# 02_-_Microcontroller.net
KiCad netlist of a schematic drawn in Altium Designer
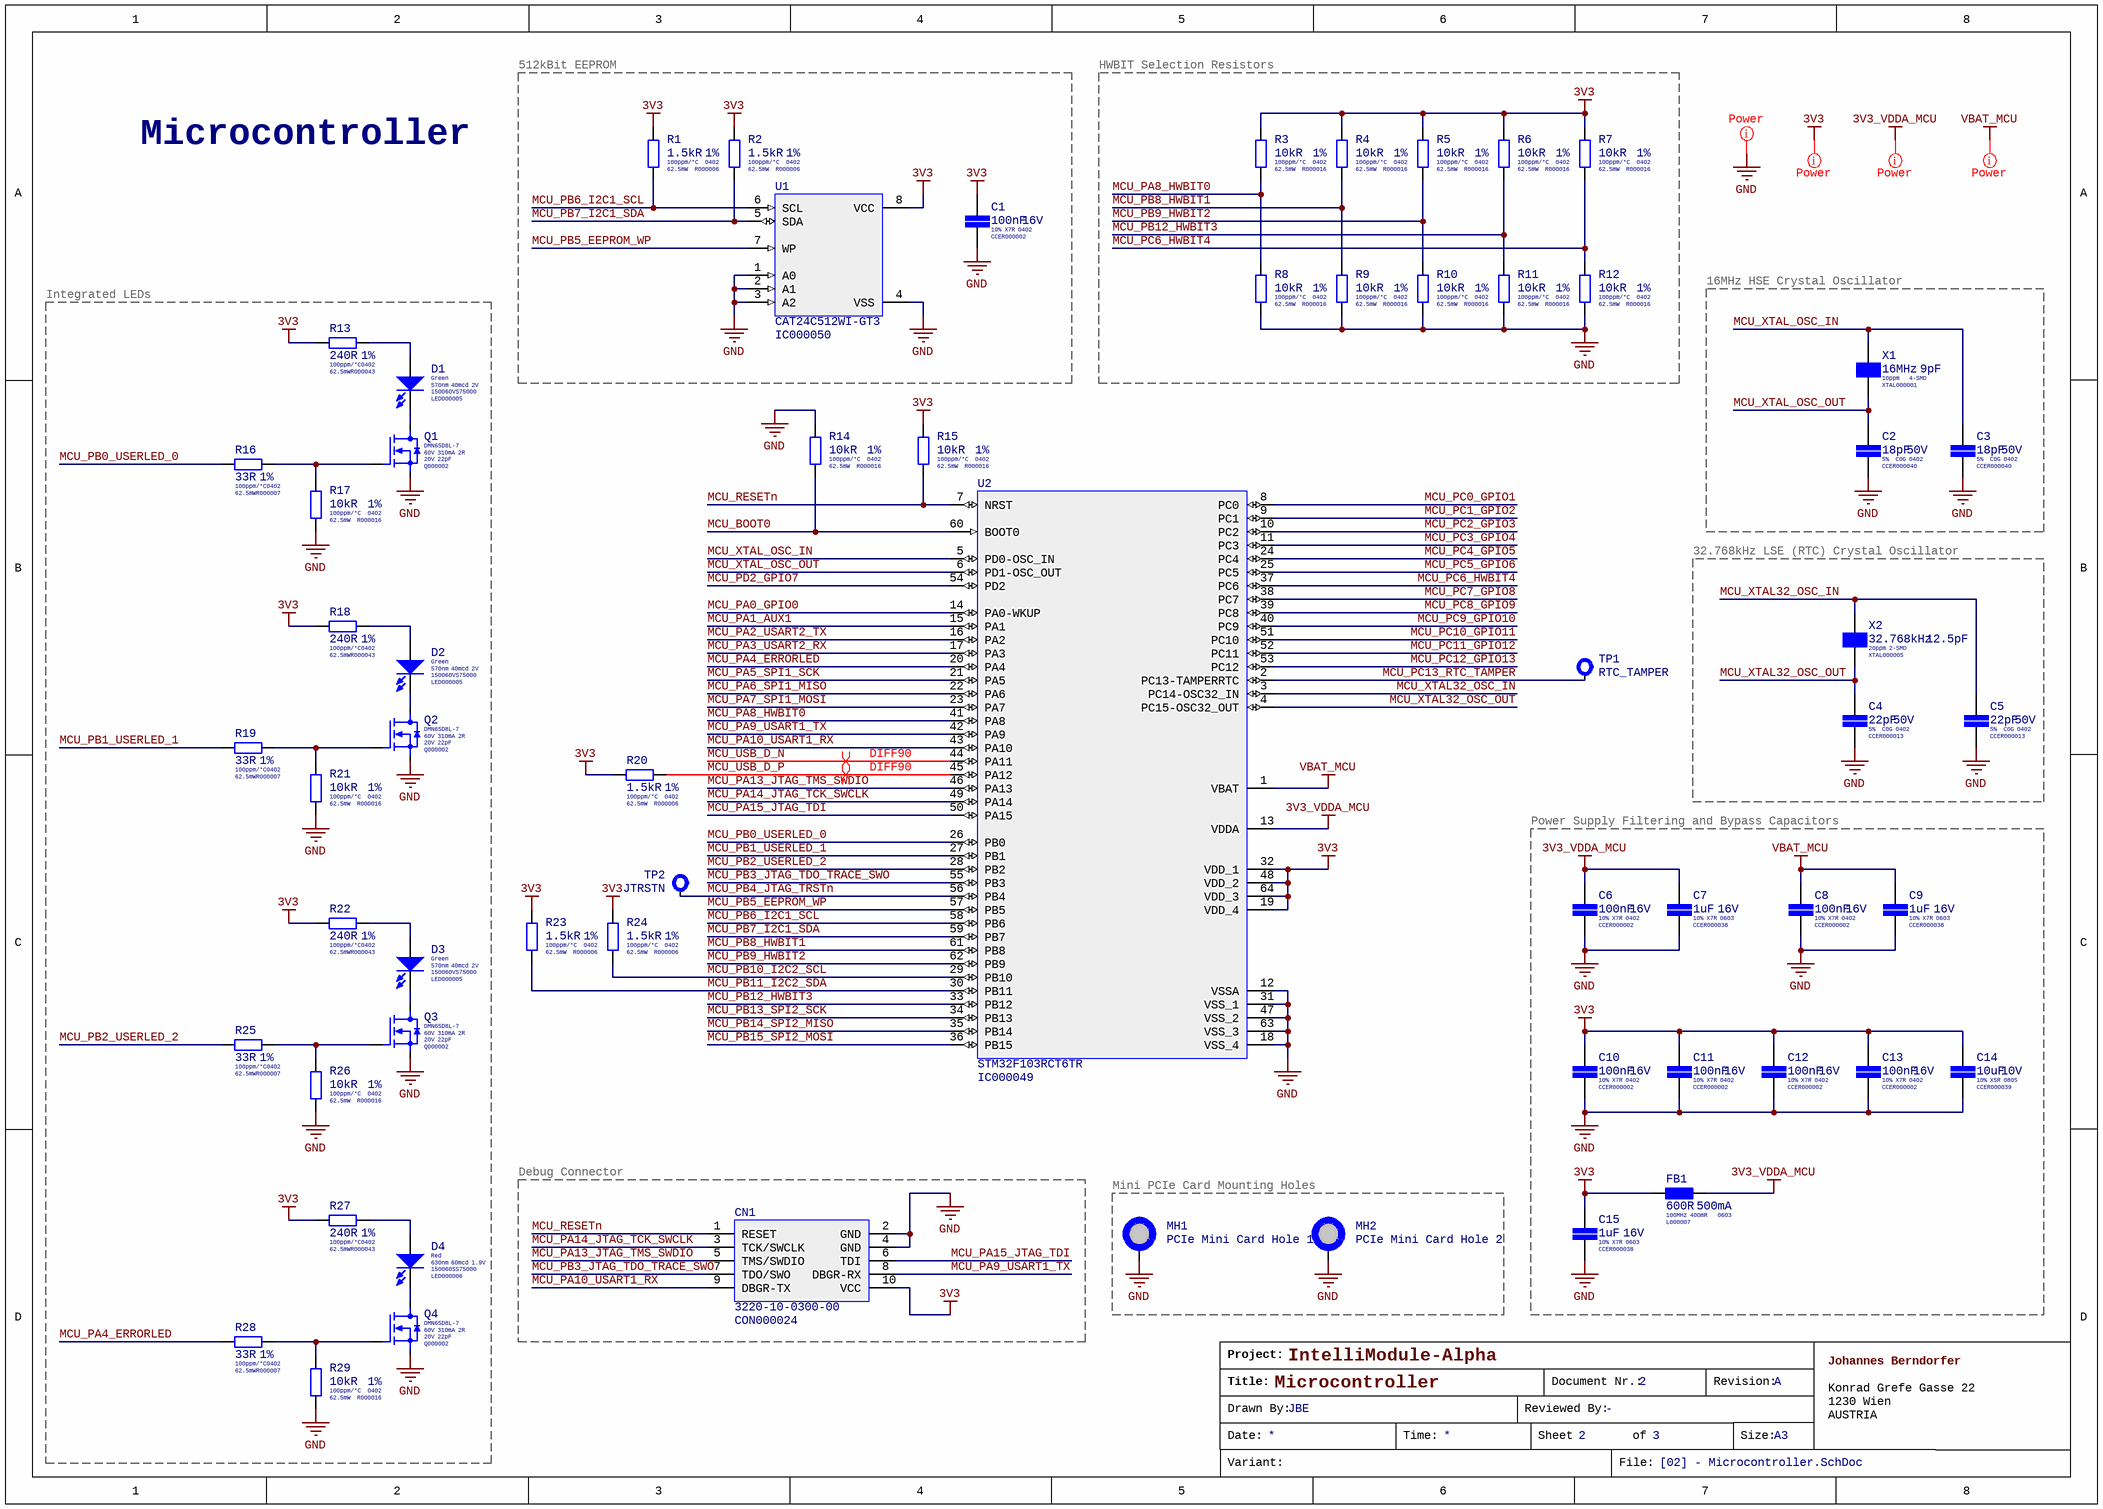
[diagram p0: [02] - Microcontroller.SchDoc]

(export (version "E")
  (design (tool "Eeschema 10.0.6"))
  (components
    (comp (ref "C1")
      (value "100nF 16V")
      (footprint "CAP-SMD-0402-0.55MM-IPC-MED")
      (description "CAP CER 100N 16V X7R 10% SMD 0402 125C SAMSUNG")
      (fields
        (field (name "VOLTAGE") "16V")
        (field (name "TOLERANCE") "10%")
        (field (name "INTERNAL PART NUMBER") "CCER000002")
        (field (name "VOLTAGE RATING (DC)") "16V")
        (field (name "DIELECTRIC") "X7R")
        (field (name "CASE/PACKAGE") "0402")
        (field (name "CAPACITANCE") "100nF")
      )
      (libsource (lib "Altium_Lib_Standard") (part "CL05B104KO5NNNC"))
    )
    (comp (ref "C2")
      (value "18pF 50V")
      (footprint "CAP-SMD-0402-0.55MM-IPC-MED")
      (description "CAP CER 18P 50V C0G 5% SMD 0402 125C YAGEO")
      (fields
        (field (name "VOLTAGE") "50V")
        (field (name "INTERNAL PART NUMBER") "CCER000040")
        (field (name "CASE/PACKAGE") "0402")
        (field (name "DIELECTRIC") "C0G")
        (field (name "TOLERANCE") "5%")
        (field (name "VOLTAGE RATING") "50V")
        (field (name "CAPACITANCE") "18pF")
      )
      (libsource (lib "Altium_Lib_Standard") (part "CC0402JRNPO9BN180"))
    )
    (comp (ref "C3")
      (value "18pF 50V")
      (footprint "CAP-SMD-0402-0.55MM-IPC-MED")
      (description "CAP CER 18P 50V C0G 5% SMD 0402 125C YAGEO")
      (fields
        (field (name "VOLTAGE") "50V")
        (field (name "INTERNAL PART NUMBER") "CCER000040")
        (field (name "CASE/PACKAGE") "0402")
        (field (name "DIELECTRIC") "C0G")
        (field (name "TOLERANCE") "5%")
        (field (name "VOLTAGE RATING") "50V")
        (field (name "CAPACITANCE") "18pF")
      )
      (libsource (lib "Altium_Lib_Standard") (part "CC0402JRNPO9BN180"))
    )
    (comp (ref "C4")
      (value "22pF 50V")
      (footprint "CAP-SMD-0402-0.55MM-IPC-MED")
      (description "CAP CER 22P 50V C0G 5% SMD 0402 125C SAMSUNG")
      (fields
        (field (name "MANUFACTURER") "Samsung")
        (field (name "MANUFACTURER PART NUMBER") "CL05C220JB5NNNC")
        (field (name "INTERNAL PART NUMBER") "CCER000013")
        (field (name "VOLTAGE RATING") "50V")
        (field (name "TOLERANCE") "5%")
        (field (name "DIELECTRIC") "C0G")
        (field (name "CASE/PACKAGE") "0402")
        (field (name "CAPACITANCE") "22pF")
      )
      (libsource (lib "Altium_Lib_Standard") (part "CL05C220JB5NNNC"))
    )
    (comp (ref "C5")
      (value "22pF 50V")
      (footprint "CAP-SMD-0402-0.55MM-IPC-MED")
      (description "CAP CER 22P 50V C0G 5% SMD 0402 125C SAMSUNG")
      (fields
        (field (name "MANUFACTURER") "Samsung")
        (field (name "MANUFACTURER PART NUMBER") "CL05C220JB5NNNC")
        (field (name "INTERNAL PART NUMBER") "CCER000013")
        (field (name "VOLTAGE RATING") "50V")
        (field (name "TOLERANCE") "5%")
        (field (name "DIELECTRIC") "C0G")
        (field (name "CASE/PACKAGE") "0402")
        (field (name "CAPACITANCE") "22pF")
      )
      (libsource (lib "Altium_Lib_Standard") (part "CL05C220JB5NNNC"))
    )
    (comp (ref "C6")
      (value "100nF 16V")
      (footprint "CAP-SMD-0402-0.55MM-IPC-MED")
      (description "CAP CER 100N 16V X7R 10% SMD 0402 125C SAMSUNG")
      (fields
        (field (name "VOLTAGE") "16V")
        (field (name "TOLERANCE") "10%")
        (field (name "INTERNAL PART NUMBER") "CCER000002")
        (field (name "VOLTAGE RATING (DC)") "16V")
        (field (name "DIELECTRIC") "X7R")
        (field (name "CASE/PACKAGE") "0402")
        (field (name "CAPACITANCE") "100nF")
      )
      (libsource (lib "Altium_Lib_Standard") (part "CL05B104KO5NNNC"))
    )
    (comp (ref "C7")
      (value "1uF 16V")
      (footprint "CAP-SMD-0603-0.9MM-IPC-MED")
      (description "CAP CER 1U 16V X7R 10% SMD 0603 125C SAMSUNG")
      (fields
        (field (name "INTERNAL PART NUMBER") "CCER000038")
        (field (name "CAPACITANCE") "1uF")
        (field (name "VOLTAGE") "16V")
        (field (name "TOLERANCE") "10%")
        (field (name "DIELECTRIC") "X7R")
        (field (name "CASE/PACKAGE") "0603")
      )
      (libsource (lib "Altium_Lib_Standard") (part "CL10B105KO8NNNC"))
    )
    (comp (ref "C8")
      (value "100nF 16V")
      (footprint "CAP-SMD-0402-0.55MM-IPC-MED")
      (description "CAP CER 100N 16V X7R 10% SMD 0402 125C SAMSUNG")
      (fields
        (field (name "VOLTAGE") "16V")
        (field (name "TOLERANCE") "10%")
        (field (name "INTERNAL PART NUMBER") "CCER000002")
        (field (name "VOLTAGE RATING (DC)") "16V")
        (field (name "DIELECTRIC") "X7R")
        (field (name "CASE/PACKAGE") "0402")
        (field (name "CAPACITANCE") "100nF")
      )
      (libsource (lib "Altium_Lib_Standard") (part "CL05B104KO5NNNC"))
    )
    (comp (ref "C9")
      (value "1uF 16V")
      (footprint "CAP-SMD-0603-0.9MM-IPC-MED")
      (description "CAP CER 1U 16V X7R 10% SMD 0603 125C SAMSUNG")
      (fields
        (field (name "INTERNAL PART NUMBER") "CCER000038")
        (field (name "CAPACITANCE") "1uF")
        (field (name "VOLTAGE") "16V")
        (field (name "TOLERANCE") "10%")
        (field (name "DIELECTRIC") "X7R")
        (field (name "CASE/PACKAGE") "0603")
      )
      (libsource (lib "Altium_Lib_Standard") (part "CL10B105KO8NNNC"))
    )
    (comp (ref "C10")
      (value "100nF 16V")
      (footprint "CAP-SMD-0402-0.55MM-IPC-MED")
      (description "CAP CER 100N 16V X7R 10% SMD 0402 125C SAMSUNG")
      (fields
        (field (name "VOLTAGE") "16V")
        (field (name "TOLERANCE") "10%")
        (field (name "INTERNAL PART NUMBER") "CCER000002")
        (field (name "VOLTAGE RATING (DC)") "16V")
        (field (name "DIELECTRIC") "X7R")
        (field (name "CASE/PACKAGE") "0402")
        (field (name "CAPACITANCE") "100nF")
      )
      (libsource (lib "Altium_Lib_Standard") (part "CL05B104KO5NNNC"))
    )
    (comp (ref "C11")
      (value "100nF 16V")
      (footprint "CAP-SMD-0402-0.55MM-IPC-MED")
      (description "CAP CER 100N 16V X7R 10% SMD 0402 125C SAMSUNG")
      (fields
        (field (name "VOLTAGE") "16V")
        (field (name "TOLERANCE") "10%")
        (field (name "INTERNAL PART NUMBER") "CCER000002")
        (field (name "VOLTAGE RATING (DC)") "16V")
        (field (name "DIELECTRIC") "X7R")
        (field (name "CASE/PACKAGE") "0402")
        (field (name "CAPACITANCE") "100nF")
      )
      (libsource (lib "Altium_Lib_Standard") (part "CL05B104KO5NNNC"))
    )
    (comp (ref "C12")
      (value "100nF 16V")
      (footprint "CAP-SMD-0402-0.55MM-IPC-MED")
      (description "CAP CER 100N 16V X7R 10% SMD 0402 125C SAMSUNG")
      (fields
        (field (name "VOLTAGE") "16V")
        (field (name "TOLERANCE") "10%")
        (field (name "INTERNAL PART NUMBER") "CCER000002")
        (field (name "VOLTAGE RATING (DC)") "16V")
        (field (name "DIELECTRIC") "X7R")
        (field (name "CASE/PACKAGE") "0402")
        (field (name "CAPACITANCE") "100nF")
      )
      (libsource (lib "Altium_Lib_Standard") (part "CL05B104KO5NNNC"))
    )
    (comp (ref "C13")
      (value "100nF 16V")
      (footprint "CAP-SMD-0402-0.55MM-IPC-MED")
      (description "CAP CER 100N 16V X7R 10% SMD 0402 125C SAMSUNG")
      (fields
        (field (name "VOLTAGE") "16V")
        (field (name "TOLERANCE") "10%")
        (field (name "INTERNAL PART NUMBER") "CCER000002")
        (field (name "VOLTAGE RATING (DC)") "16V")
        (field (name "DIELECTRIC") "X7R")
        (field (name "CASE/PACKAGE") "0402")
        (field (name "CAPACITANCE") "100nF")
      )
      (libsource (lib "Altium_Lib_Standard") (part "CL05B104KO5NNNC"))
    )
    (comp (ref "C14")
      (value "10uF 10V")
      (footprint "CAP-SMD-0805-1.35MM-IPC-MED")
      (description "CAP CER 10U 10V X5R 10% SMD 0805 85C SAMSUNG")
      (fields
        (field (name "VOLTAGE") "10V")
        (field (name "INTERNAL PART NUMBER") "CCER000039")
        (field (name "TOLERANCE") "10%")
        (field (name "VOLTAGE RATING") "10V")
        (field (name "DIELECTRIC") "X5R")
        (field (name "CASE/PACKAGE") "0805")
        (field (name "CAPACITANCE") "10uF")
      )
      (libsource (lib "Altium_Lib_Standard") (part "CL21A106KPFNNNG"))
    )
    (comp (ref "C15")
      (value "1uF 16V")
      (footprint "CAP-SMD-0603-0.9MM-IPC-MED")
      (description "CAP CER 1U 16V X7R 10% SMD 0603 125C SAMSUNG")
      (fields
        (field (name "INTERNAL PART NUMBER") "CCER000038")
        (field (name "CAPACITANCE") "1uF")
        (field (name "VOLTAGE") "16V")
        (field (name "TOLERANCE") "10%")
        (field (name "DIELECTRIC") "X7R")
        (field (name "CASE/PACKAGE") "0603")
      )
      (libsource (lib "Altium_Lib_Standard") (part "CL10B105KO8NNNC"))
    )
    (comp (ref "CN1")
      (value "3220-10-0300-00")
      (footprint "CON-SMD-PINHEADER-SHIELDED-1.27MM-10POS-2X5-3220-10-0300-00-CNC-TECH")
      (description "CON PINHDR SMD 1.27MM SHIELDED KEYED CNC TECH 10POS")
      (fields (field (name "INTERNAL PART NUMBER") "CON000024"))
      (libsource (lib "Altium_Lib_Standard") (part "3220-10-0300-00"))
    )
    (comp (ref "D1")
      (value "150060VS75000")
      (footprint "LED-SMD-0603")
      (description "LED GREEN570NM SMD 0603 2V 20mA 40mcd")
      (fields
        (field (name "MANUFACTURER") "Wurth Electronics")
        (field (name "LUMINOUS INTENSITY") "40mcd")
        (field (name "FORWARD VOLTAGE") "2V")
        (field (name "COLOR") "Green")
        (field (name "MANUFACTURER PART NUMBER") "150060VS75000")
        (field (name "WAVELENGTH") "570nm")
        (field (name "INTERNAL PART NUMBER") "LED000005")
      )
      (libsource (lib "Altium_Lib_Standard") (part "150060VS75000"))
    )
    (comp (ref "D2")
      (value "150060VS75000")
      (footprint "LED-SMD-0603")
      (description "LED GREEN570NM SMD 0603 2V 20mA 40mcd")
      (fields
        (field (name "MANUFACTURER") "Wurth Electronics")
        (field (name "LUMINOUS INTENSITY") "40mcd")
        (field (name "FORWARD VOLTAGE") "2V")
        (field (name "COLOR") "Green")
        (field (name "MANUFACTURER PART NUMBER") "150060VS75000")
        (field (name "WAVELENGTH") "570nm")
        (field (name "INTERNAL PART NUMBER") "LED000005")
      )
      (libsource (lib "Altium_Lib_Standard") (part "150060VS75000"))
    )
    (comp (ref "D3")
      (value "150060VS75000")
      (footprint "LED-SMD-0603")
      (description "LED GREEN570NM SMD 0603 2V 20mA 40mcd")
      (fields
        (field (name "MANUFACTURER") "Wurth Electronics")
        (field (name "LUMINOUS INTENSITY") "40mcd")
        (field (name "FORWARD VOLTAGE") "2V")
        (field (name "COLOR") "Green")
        (field (name "MANUFACTURER PART NUMBER") "150060VS75000")
        (field (name "WAVELENGTH") "570nm")
        (field (name "INTERNAL PART NUMBER") "LED000005")
      )
      (libsource (lib "Altium_Lib_Standard") (part "150060VS75000"))
    )
    (comp (ref "D4")
      (value "150060SS75000")
      (footprint "LED-SMD-0603")
      (description "LED RED630NM SMD 0603 1V9 20mA 60mcd")
      (fields
        (field (name "MANUFACTURER") "Wurth Electronics")
        (field (name "MANUFACTURER PART NUMBER") "150060SS75000")
        (field (name "INTERNAL PART NUMBER") "LED000006")
        (field (name "LUMINOUS INTENSITY") "60mcd")
        (field (name "FORWARD VOLTAGE") "1.9V")
        (field (name "DOMINANT WAVELENGTH") "630nm")
        (field (name "COLOR") "Red")
      )
      (libsource (lib "Altium_Lib_Standard") (part "150060SS75000"))
    )
    (comp (ref "FB1")
      (value "600R-100MHz 500MA")
      (footprint "IND-SMD-0603-0.75MM-IPC-MED")
      (description "BEAD 600R@100MHZ 500MA 400mR SMD 0603 FERRITE TDK")
      (fields
        (field (name "TOLERANCE") "25%")
        (field (name "INTERNAL PART NUMBER") "L000007")
        (field (name "MAX DC CURRENT") "500mA")
        (field (name "IMPEDANCE") "600R")
        (field (name "DC RESISTANCE (DCR)") "400mR")
        (field (name "CASE/PACKAGE") "0603")
      )
      (libsource (lib "Altium_Lib_Standard") (part "MMZ1608B601CTAH0"))
    )
    (comp (ref "MH1")
      (value "PCIe Mini Card Hole 1")
      (footprint "MECH-HOLE-PTH-2.6MM-5.8MMSQ-PCIEMINI")
      (description "2.6mm Diameter 5.8mm Square Pad Plated Through Hole for PCIe-Mini Cards")
      (libsource (lib "Altium_Lib_Standard") (part "MECH-HOLE-PTH-2.6MM-5.8MMSQ-PCIEMINI"))
    )
    (comp (ref "MH2")
      (value "PCIe Mini Card Hole 2")
      (footprint "MECH-HOLE-PTH-2.6MM-5.8MMSQ-PCIEMINI")
      (description "2.6mm Diameter 5.8mm Square Pad Plated Through Hole for PCIe-Mini Cards")
      (libsource (lib "Altium_Lib_Standard") (part "MECH-HOLE-PTH-2.6MM-5.8MMSQ-PCIEMINI"))
    )
    (comp (ref "Q1")
      (value "DMN65D8L-7")
      (footprint "SOT-23-3-H1.1MM-DIODES-INC")
      (description "TRANSISTOR MOSFET N-CH 60V 310mA 2R SOT-23")
      (fields
        (field (name "MANUFACTURER") "Diodes")
        (field (name "MANUFACTURER PART NUMBER") "DMN65D8L-7")
        (field (name "DRAIN TO SOURCE RESISTANCE") "2R")
        (field (name "CONTINUOUS DRAIN CURRENT (ID)") "310mA")
        (field (name "DRAIN TO SOURCE BREAKDOWN VOLTAGE") "60V")
        (field (name "GATE TO SOURCE VOLTAGE (VGS)") "20V")
        (field (name "INPUT CAPACITANCE") "22pF")
        (field (name "INTERNAL PART NUMBER") "Q000002")
      )
      (libsource (lib "Altium_Lib_Standard") (part "DMN65D8L-7"))
    )
    (comp (ref "Q2")
      (value "DMN65D8L-7")
      (footprint "SOT-23-3-H1.1MM-DIODES-INC")
      (description "TRANSISTOR MOSFET N-CH 60V 310mA 2R SOT-23")
      (fields
        (field (name "MANUFACTURER") "Diodes")
        (field (name "MANUFACTURER PART NUMBER") "DMN65D8L-7")
        (field (name "DRAIN TO SOURCE RESISTANCE") "2R")
        (field (name "CONTINUOUS DRAIN CURRENT (ID)") "310mA")
        (field (name "DRAIN TO SOURCE BREAKDOWN VOLTAGE") "60V")
        (field (name "GATE TO SOURCE VOLTAGE (VGS)") "20V")
        (field (name "INPUT CAPACITANCE") "22pF")
        (field (name "INTERNAL PART NUMBER") "Q000002")
      )
      (libsource (lib "Altium_Lib_Standard") (part "DMN65D8L-7"))
    )
    (comp (ref "Q3")
      (value "DMN65D8L-7")
      (footprint "SOT-23-3-H1.1MM-DIODES-INC")
      (description "TRANSISTOR MOSFET N-CH 60V 310mA 2R SOT-23")
      (fields
        (field (name "MANUFACTURER") "Diodes")
        (field (name "MANUFACTURER PART NUMBER") "DMN65D8L-7")
        (field (name "DRAIN TO SOURCE RESISTANCE") "2R")
        (field (name "CONTINUOUS DRAIN CURRENT (ID)") "310mA")
        (field (name "DRAIN TO SOURCE BREAKDOWN VOLTAGE") "60V")
        (field (name "GATE TO SOURCE VOLTAGE (VGS)") "20V")
        (field (name "INPUT CAPACITANCE") "22pF")
        (field (name "INTERNAL PART NUMBER") "Q000002")
      )
      (libsource (lib "Altium_Lib_Standard") (part "DMN65D8L-7"))
    )
    (comp (ref "Q4")
      (value "DMN65D8L-7")
      (footprint "SOT-23-3-H1.1MM-DIODES-INC")
      (description "TRANSISTOR MOSFET N-CH 60V 310mA 2R SOT-23")
      (fields
        (field (name "MANUFACTURER") "Diodes")
        (field (name "MANUFACTURER PART NUMBER") "DMN65D8L-7")
        (field (name "DRAIN TO SOURCE RESISTANCE") "2R")
        (field (name "CONTINUOUS DRAIN CURRENT (ID)") "310mA")
        (field (name "DRAIN TO SOURCE BREAKDOWN VOLTAGE") "60V")
        (field (name "GATE TO SOURCE VOLTAGE (VGS)") "20V")
        (field (name "INPUT CAPACITANCE") "22pF")
        (field (name "INTERNAL PART NUMBER") "Q000002")
      )
      (libsource (lib "Altium_Lib_Standard") (part "DMN65D8L-7"))
    )
    (comp (ref "R1")
      (value "1.5kR 1%")
      (footprint "RES-SMD-0402-0.4MM-IPC-MED")
      (description "RES 1K5 1% 1/16W SMD 0402 YAEGO")
      (fields
        (field (name "MANUFACTURER") "Yageo")
        (field (name "MANUFACTURER PART NUMBER") "RC0402FR-071K5L")
        (field (name "TEMPERATURE COEFFICIENT") "100ppm/°C")
        (field (name "TOLERANCE") "1%")
        (field (name "RESISTANCE") "1.5kR")
        (field (name "MAX POWER DISSIPATION") "62.5mW")
        (field (name "CASE/PACKAGE") "0402")
        (field (name "INTERNAL PART NUMBER") "R000006")
      )
      (libsource (lib "Altium_Lib_Standard") (part "RC0402FR-071K5L"))
    )
    (comp (ref "R2")
      (value "1.5kR 1%")
      (footprint "RES-SMD-0402-0.4MM-IPC-MED")
      (description "RES 1K5 1% 1/16W SMD 0402 YAEGO")
      (fields
        (field (name "MANUFACTURER") "Yageo")
        (field (name "MANUFACTURER PART NUMBER") "RC0402FR-071K5L")
        (field (name "TEMPERATURE COEFFICIENT") "100ppm/°C")
        (field (name "TOLERANCE") "1%")
        (field (name "RESISTANCE") "1.5kR")
        (field (name "MAX POWER DISSIPATION") "62.5mW")
        (field (name "CASE/PACKAGE") "0402")
        (field (name "INTERNAL PART NUMBER") "R000006")
      )
      (libsource (lib "Altium_Lib_Standard") (part "RC0402FR-071K5L"))
    )
    (comp (ref "R3")
      (value "10kR 1%")
      (footprint "RES-SMD-0402-0.4MM-IPC-MED")
      (description "RES 10K 1% 1/16W SMD 0402 YAEGO")
      (fields
        (field (name "MANUFACTURER") "Yageo")
        (field (name "MANUFACTURER PART NUMBER") "RC0402FR-0710KL")
        (field (name "TOLERANCE") "1%")
        (field (name "TEMPERATURE COEFFICIENT") "100ppm/°C")
        (field (name "RESISTANCE") "10kR")
        (field (name "POWER RATING") "62.5mW")
        (field (name "CASE CODE (IMPERIAL)") "0402")
        (field (name "INTERNAL PART NUMBER") "R000016")
      )
      (libsource (lib "Altium_Lib_Standard") (part "RC0402FR-0710KL"))
    )
    (comp (ref "R4")
      (value "10kR 1%")
      (footprint "RES-SMD-0402-0.4MM-IPC-MED")
      (description "RES 10K 1% 1/16W SMD 0402 YAEGO")
      (fields
        (field (name "MANUFACTURER") "Yageo")
        (field (name "MANUFACTURER PART NUMBER") "RC0402FR-0710KL")
        (field (name "TOLERANCE") "1%")
        (field (name "TEMPERATURE COEFFICIENT") "100ppm/°C")
        (field (name "RESISTANCE") "10kR")
        (field (name "POWER RATING") "62.5mW")
        (field (name "CASE CODE (IMPERIAL)") "0402")
        (field (name "INTERNAL PART NUMBER") "R000016")
      )
      (libsource (lib "Altium_Lib_Standard") (part "RC0402FR-0710KL"))
    )
    (comp (ref "R5")
      (value "10kR 1%")
      (footprint "RES-SMD-0402-0.4MM-IPC-MED")
      (description "RES 10K 1% 1/16W SMD 0402 YAEGO")
      (fields
        (field (name "MANUFACTURER") "Yageo")
        (field (name "MANUFACTURER PART NUMBER") "RC0402FR-0710KL")
        (field (name "TOLERANCE") "1%")
        (field (name "TEMPERATURE COEFFICIENT") "100ppm/°C")
        (field (name "RESISTANCE") "10kR")
        (field (name "POWER RATING") "62.5mW")
        (field (name "CASE CODE (IMPERIAL)") "0402")
        (field (name "INTERNAL PART NUMBER") "R000016")
      )
      (libsource (lib "Altium_Lib_Standard") (part "RC0402FR-0710KL"))
    )
    (comp (ref "R6")
      (value "10kR 1%")
      (footprint "RES-SMD-0402-0.4MM-IPC-MED")
      (description "RES 10K 1% 1/16W SMD 0402 YAEGO")
      (fields
        (field (name "MANUFACTURER") "Yageo")
        (field (name "MANUFACTURER PART NUMBER") "RC0402FR-0710KL")
        (field (name "TOLERANCE") "1%")
        (field (name "TEMPERATURE COEFFICIENT") "100ppm/°C")
        (field (name "RESISTANCE") "10kR")
        (field (name "POWER RATING") "62.5mW")
        (field (name "CASE CODE (IMPERIAL)") "0402")
        (field (name "INTERNAL PART NUMBER") "R000016")
      )
      (libsource (lib "Altium_Lib_Standard") (part "RC0402FR-0710KL"))
    )
    (comp (ref "R7")
      (value "10kR 1%")
      (footprint "RES-SMD-0402-0.4MM-IPC-MED")
      (description "RES 10K 1% 1/16W SMD 0402 YAEGO")
      (fields
        (field (name "MANUFACTURER") "Yageo")
        (field (name "MANUFACTURER PART NUMBER") "RC0402FR-0710KL")
        (field (name "TOLERANCE") "1%")
        (field (name "TEMPERATURE COEFFICIENT") "100ppm/°C")
        (field (name "RESISTANCE") "10kR")
        (field (name "POWER RATING") "62.5mW")
        (field (name "CASE CODE (IMPERIAL)") "0402")
        (field (name "INTERNAL PART NUMBER") "R000016")
      )
      (libsource (lib "Altium_Lib_Standard") (part "RC0402FR-0710KL"))
    )
    (comp (ref "R8")
      (value "10kR 1%")
      (footprint "RES-SMD-0402-0.4MM-IPC-MED")
      (description "RES 10K 1% 1/16W SMD 0402 YAEGO")
      (fields
        (field (name "MANUFACTURER") "Yageo")
        (field (name "MANUFACTURER PART NUMBER") "RC0402FR-0710KL")
        (field (name "TOLERANCE") "1%")
        (field (name "TEMPERATURE COEFFICIENT") "100ppm/°C")
        (field (name "RESISTANCE") "10kR")
        (field (name "POWER RATING") "62.5mW")
        (field (name "CASE CODE (IMPERIAL)") "0402")
        (field (name "INTERNAL PART NUMBER") "R000016")
      )
      (libsource (lib "Altium_Lib_Standard") (part "RC0402FR-0710KL"))
    )
    (comp (ref "R9")
      (value "10kR 1%")
      (footprint "RES-SMD-0402-0.4MM-IPC-MED")
      (description "RES 10K 1% 1/16W SMD 0402 YAEGO")
      (fields
        (field (name "MANUFACTURER") "Yageo")
        (field (name "MANUFACTURER PART NUMBER") "RC0402FR-0710KL")
        (field (name "TOLERANCE") "1%")
        (field (name "TEMPERATURE COEFFICIENT") "100ppm/°C")
        (field (name "RESISTANCE") "10kR")
        (field (name "POWER RATING") "62.5mW")
        (field (name "CASE CODE (IMPERIAL)") "0402")
        (field (name "INTERNAL PART NUMBER") "R000016")
      )
      (libsource (lib "Altium_Lib_Standard") (part "RC0402FR-0710KL"))
    )
    (comp (ref "R10")
      (value "10kR 1%")
      (footprint "RES-SMD-0402-0.4MM-IPC-MED")
      (description "RES 10K 1% 1/16W SMD 0402 YAEGO")
      (fields
        (field (name "MANUFACTURER") "Yageo")
        (field (name "MANUFACTURER PART NUMBER") "RC0402FR-0710KL")
        (field (name "TOLERANCE") "1%")
        (field (name "TEMPERATURE COEFFICIENT") "100ppm/°C")
        (field (name "RESISTANCE") "10kR")
        (field (name "POWER RATING") "62.5mW")
        (field (name "CASE CODE (IMPERIAL)") "0402")
        (field (name "INTERNAL PART NUMBER") "R000016")
      )
      (libsource (lib "Altium_Lib_Standard") (part "RC0402FR-0710KL"))
    )
    (comp (ref "R11")
      (value "10kR 1%")
      (footprint "RES-SMD-0402-0.4MM-IPC-MED")
      (description "RES 10K 1% 1/16W SMD 0402 YAEGO")
      (fields
        (field (name "MANUFACTURER") "Yageo")
        (field (name "MANUFACTURER PART NUMBER") "RC0402FR-0710KL")
        (field (name "TOLERANCE") "1%")
        (field (name "TEMPERATURE COEFFICIENT") "100ppm/°C")
        (field (name "RESISTANCE") "10kR")
        (field (name "POWER RATING") "62.5mW")
        (field (name "CASE CODE (IMPERIAL)") "0402")
        (field (name "INTERNAL PART NUMBER") "R000016")
      )
      (libsource (lib "Altium_Lib_Standard") (part "RC0402FR-0710KL"))
    )
    (comp (ref "R12")
      (value "10kR 1%")
      (footprint "RES-SMD-0402-0.4MM-IPC-MED")
      (description "RES 10K 1% 1/16W SMD 0402 YAEGO")
      (fields
        (field (name "MANUFACTURER") "Yageo")
        (field (name "MANUFACTURER PART NUMBER") "RC0402FR-0710KL")
        (field (name "TOLERANCE") "1%")
        (field (name "TEMPERATURE COEFFICIENT") "100ppm/°C")
        (field (name "RESISTANCE") "10kR")
        (field (name "POWER RATING") "62.5mW")
        (field (name "CASE CODE (IMPERIAL)") "0402")
        (field (name "INTERNAL PART NUMBER") "R000016")
      )
      (libsource (lib "Altium_Lib_Standard") (part "RC0402FR-0710KL"))
    )
    (comp (ref "R13")
      (value "240R 1%")
      (footprint "RES-SMD-0402-0.4MM-IPC-MED")
      (description "RES 240R 1% 1/16W SMD 0402 YAGEO")
      (fields
        (field (name "MANUFACTURER") "Yageo Phycomp")
        (field (name "MANUFACTURER PART NUMBER") "RC0402FR-07240RL")
        (field (name "RESISTANCE") "240R")
        (field (name "TOLERANCE") "1%")
        (field (name "TEMPERATURE COEFFICIENT") "100ppm/°C")
        (field (name "POWER RATING") "62.5mW")
        (field (name "CASE/PACKAGE") "0402")
        (field (name "INTERNAL PART NUMBER") "R000043")
      )
      (libsource (lib "Altium_Lib_Standard") (part "RC0402FR-07240RL"))
    )
    (comp (ref "R14")
      (value "10kR 1%")
      (footprint "RES-SMD-0402-0.4MM-IPC-MED")
      (description "RES 10K 1% 1/16W SMD 0402 YAEGO")
      (fields
        (field (name "MANUFACTURER") "Yageo")
        (field (name "MANUFACTURER PART NUMBER") "RC0402FR-0710KL")
        (field (name "TOLERANCE") "1%")
        (field (name "TEMPERATURE COEFFICIENT") "100ppm/°C")
        (field (name "RESISTANCE") "10kR")
        (field (name "POWER RATING") "62.5mW")
        (field (name "CASE CODE (IMPERIAL)") "0402")
        (field (name "INTERNAL PART NUMBER") "R000016")
      )
      (libsource (lib "Altium_Lib_Standard") (part "RC0402FR-0710KL"))
    )
    (comp (ref "R15")
      (value "10kR 1%")
      (footprint "RES-SMD-0402-0.4MM-IPC-MED")
      (description "RES 10K 1% 1/16W SMD 0402 YAEGO")
      (fields
        (field (name "MANUFACTURER") "Yageo")
        (field (name "MANUFACTURER PART NUMBER") "RC0402FR-0710KL")
        (field (name "TOLERANCE") "1%")
        (field (name "TEMPERATURE COEFFICIENT") "100ppm/°C")
        (field (name "RESISTANCE") "10kR")
        (field (name "POWER RATING") "62.5mW")
        (field (name "CASE CODE (IMPERIAL)") "0402")
        (field (name "INTERNAL PART NUMBER") "R000016")
      )
      (libsource (lib "Altium_Lib_Standard") (part "RC0402FR-0710KL"))
    )
    (comp (ref "R16")
      (value "33R 1%")
      (footprint "RES-SMD-0402-0.4MM-IPC-MED")
      (description "RES 33R 1% 1/16W SMD 0402 YAEGO")
      (fields
        (field (name "MANUFACTURER") "Yageo")
        (field (name "MANUFACTURER PART NUMBER") "RC0402FR-0733RL")
        (field (name "INTERNAL PART NUMBER") "R000007")
        (field (name "TEMPERATURE COEFFICIENT") "100ppm/°C")
        (field (name "CASE/PACKAGE") "0402")
        (field (name "POWER RATING") "62.5mW")
        (field (name "TOLERANCE") "1%")
        (field (name "RESISTANCE") "33R")
      )
      (libsource (lib "Altium_Lib_Standard") (part "RC0402FR-0733RL"))
    )
    (comp (ref "R17")
      (value "10kR 1%")
      (footprint "RES-SMD-0402-0.4MM-IPC-MED")
      (description "RES 10K 1% 1/16W SMD 0402 YAEGO")
      (fields
        (field (name "MANUFACTURER") "Yageo")
        (field (name "MANUFACTURER PART NUMBER") "RC0402FR-0710KL")
        (field (name "TOLERANCE") "1%")
        (field (name "TEMPERATURE COEFFICIENT") "100ppm/°C")
        (field (name "RESISTANCE") "10kR")
        (field (name "POWER RATING") "62.5mW")
        (field (name "CASE CODE (IMPERIAL)") "0402")
        (field (name "INTERNAL PART NUMBER") "R000016")
      )
      (libsource (lib "Altium_Lib_Standard") (part "RC0402FR-0710KL"))
    )
    (comp (ref "R18")
      (value "240R 1%")
      (footprint "RES-SMD-0402-0.4MM-IPC-MED")
      (description "RES 240R 1% 1/16W SMD 0402 YAGEO")
      (fields
        (field (name "MANUFACTURER") "Yageo Phycomp")
        (field (name "MANUFACTURER PART NUMBER") "RC0402FR-07240RL")
        (field (name "RESISTANCE") "240R")
        (field (name "TOLERANCE") "1%")
        (field (name "TEMPERATURE COEFFICIENT") "100ppm/°C")
        (field (name "POWER RATING") "62.5mW")
        (field (name "CASE/PACKAGE") "0402")
        (field (name "INTERNAL PART NUMBER") "R000043")
      )
      (libsource (lib "Altium_Lib_Standard") (part "RC0402FR-07240RL"))
    )
    (comp (ref "R19")
      (value "33R 1%")
      (footprint "RES-SMD-0402-0.4MM-IPC-MED")
      (description "RES 33R 1% 1/16W SMD 0402 YAEGO")
      (fields
        (field (name "MANUFACTURER") "Yageo")
        (field (name "MANUFACTURER PART NUMBER") "RC0402FR-0733RL")
        (field (name "INTERNAL PART NUMBER") "R000007")
        (field (name "TEMPERATURE COEFFICIENT") "100ppm/°C")
        (field (name "CASE/PACKAGE") "0402")
        (field (name "POWER RATING") "62.5mW")
        (field (name "TOLERANCE") "1%")
        (field (name "RESISTANCE") "33R")
      )
      (libsource (lib "Altium_Lib_Standard") (part "RC0402FR-0733RL"))
    )
    (comp (ref "R20")
      (value "1.5kR 1%")
      (footprint "RES-SMD-0402-0.4MM-IPC-MED")
      (description "RES 1K5 1% 1/16W SMD 0402 YAEGO")
      (fields
        (field (name "MANUFACTURER") "Yageo")
        (field (name "MANUFACTURER PART NUMBER") "RC0402FR-071K5L")
        (field (name "TEMPERATURE COEFFICIENT") "100ppm/°C")
        (field (name "TOLERANCE") "1%")
        (field (name "RESISTANCE") "1.5kR")
        (field (name "MAX POWER DISSIPATION") "62.5mW")
        (field (name "CASE/PACKAGE") "0402")
        (field (name "INTERNAL PART NUMBER") "R000006")
      )
      (libsource (lib "Altium_Lib_Standard") (part "RC0402FR-071K5L"))
    )
    (comp (ref "R21")
      (value "10kR 1%")
      (footprint "RES-SMD-0402-0.4MM-IPC-MED")
      (description "RES 10K 1% 1/16W SMD 0402 YAEGO")
      (fields
        (field (name "MANUFACTURER") "Yageo")
        (field (name "MANUFACTURER PART NUMBER") "RC0402FR-0710KL")
        (field (name "TOLERANCE") "1%")
        (field (name "TEMPERATURE COEFFICIENT") "100ppm/°C")
        (field (name "RESISTANCE") "10kR")
        (field (name "POWER RATING") "62.5mW")
        (field (name "CASE CODE (IMPERIAL)") "0402")
        (field (name "INTERNAL PART NUMBER") "R000016")
      )
      (libsource (lib "Altium_Lib_Standard") (part "RC0402FR-0710KL"))
    )
    (comp (ref "R22")
      (value "240R 1%")
      (footprint "RES-SMD-0402-0.4MM-IPC-MED")
      (description "RES 240R 1% 1/16W SMD 0402 YAGEO")
      (fields
        (field (name "MANUFACTURER") "Yageo Phycomp")
        (field (name "MANUFACTURER PART NUMBER") "RC0402FR-07240RL")
        (field (name "RESISTANCE") "240R")
        (field (name "TOLERANCE") "1%")
        (field (name "TEMPERATURE COEFFICIENT") "100ppm/°C")
        (field (name "POWER RATING") "62.5mW")
        (field (name "CASE/PACKAGE") "0402")
        (field (name "INTERNAL PART NUMBER") "R000043")
      )
      (libsource (lib "Altium_Lib_Standard") (part "RC0402FR-07240RL"))
    )
    (comp (ref "R23")
      (value "1.5kR 1%")
      (footprint "RES-SMD-0402-0.4MM-IPC-MED")
      (description "RES 1K5 1% 1/16W SMD 0402 YAEGO")
      (fields
        (field (name "MANUFACTURER") "Yageo")
        (field (name "MANUFACTURER PART NUMBER") "RC0402FR-071K5L")
        (field (name "TEMPERATURE COEFFICIENT") "100ppm/°C")
        (field (name "TOLERANCE") "1%")
        (field (name "RESISTANCE") "1.5kR")
        (field (name "MAX POWER DISSIPATION") "62.5mW")
        (field (name "CASE/PACKAGE") "0402")
        (field (name "INTERNAL PART NUMBER") "R000006")
      )
      (libsource (lib "Altium_Lib_Standard") (part "RC0402FR-071K5L"))
    )
    (comp (ref "R24")
      (value "1.5kR 1%")
      (footprint "RES-SMD-0402-0.4MM-IPC-MED")
      (description "RES 1K5 1% 1/16W SMD 0402 YAEGO")
      (fields
        (field (name "MANUFACTURER") "Yageo")
        (field (name "MANUFACTURER PART NUMBER") "RC0402FR-071K5L")
        (field (name "TEMPERATURE COEFFICIENT") "100ppm/°C")
        (field (name "TOLERANCE") "1%")
        (field (name "RESISTANCE") "1.5kR")
        (field (name "MAX POWER DISSIPATION") "62.5mW")
        (field (name "CASE/PACKAGE") "0402")
        (field (name "INTERNAL PART NUMBER") "R000006")
      )
      (libsource (lib "Altium_Lib_Standard") (part "RC0402FR-071K5L"))
    )
    (comp (ref "R25")
      (value "33R 1%")
      (footprint "RES-SMD-0402-0.4MM-IPC-MED")
      (description "RES 33R 1% 1/16W SMD 0402 YAEGO")
      (fields
        (field (name "MANUFACTURER") "Yageo")
        (field (name "MANUFACTURER PART NUMBER") "RC0402FR-0733RL")
        (field (name "INTERNAL PART NUMBER") "R000007")
        (field (name "TEMPERATURE COEFFICIENT") "100ppm/°C")
        (field (name "CASE/PACKAGE") "0402")
        (field (name "POWER RATING") "62.5mW")
        (field (name "TOLERANCE") "1%")
        (field (name "RESISTANCE") "33R")
      )
      (libsource (lib "Altium_Lib_Standard") (part "RC0402FR-0733RL"))
    )
    (comp (ref "R26")
      (value "10kR 1%")
      (footprint "RES-SMD-0402-0.4MM-IPC-MED")
      (description "RES 10K 1% 1/16W SMD 0402 YAEGO")
      (fields
        (field (name "MANUFACTURER") "Yageo")
        (field (name "MANUFACTURER PART NUMBER") "RC0402FR-0710KL")
        (field (name "TOLERANCE") "1%")
        (field (name "TEMPERATURE COEFFICIENT") "100ppm/°C")
        (field (name "RESISTANCE") "10kR")
        (field (name "POWER RATING") "62.5mW")
        (field (name "CASE CODE (IMPERIAL)") "0402")
        (field (name "INTERNAL PART NUMBER") "R000016")
      )
      (libsource (lib "Altium_Lib_Standard") (part "RC0402FR-0710KL"))
    )
    (comp (ref "R27")
      (value "240R 1%")
      (footprint "RES-SMD-0402-0.4MM-IPC-MED")
      (description "RES 240R 1% 1/16W SMD 0402 YAGEO")
      (fields
        (field (name "MANUFACTURER") "Yageo Phycomp")
        (field (name "MANUFACTURER PART NUMBER") "RC0402FR-07240RL")
        (field (name "RESISTANCE") "240R")
        (field (name "TOLERANCE") "1%")
        (field (name "TEMPERATURE COEFFICIENT") "100ppm/°C")
        (field (name "POWER RATING") "62.5mW")
        (field (name "CASE/PACKAGE") "0402")
        (field (name "INTERNAL PART NUMBER") "R000043")
      )
      (libsource (lib "Altium_Lib_Standard") (part "RC0402FR-07240RL"))
    )
    (comp (ref "R28")
      (value "33R 1%")
      (footprint "RES-SMD-0402-0.4MM-IPC-MED")
      (description "RES 33R 1% 1/16W SMD 0402 YAEGO")
      (fields
        (field (name "MANUFACTURER") "Yageo")
        (field (name "MANUFACTURER PART NUMBER") "RC0402FR-0733RL")
        (field (name "INTERNAL PART NUMBER") "R000007")
        (field (name "TEMPERATURE COEFFICIENT") "100ppm/°C")
        (field (name "CASE/PACKAGE") "0402")
        (field (name "POWER RATING") "62.5mW")
        (field (name "TOLERANCE") "1%")
        (field (name "RESISTANCE") "33R")
      )
      (libsource (lib "Altium_Lib_Standard") (part "RC0402FR-0733RL"))
    )
    (comp (ref "R29")
      (value "10kR 1%")
      (footprint "RES-SMD-0402-0.4MM-IPC-MED")
      (description "RES 10K 1% 1/16W SMD 0402 YAEGO")
      (fields
        (field (name "MANUFACTURER") "Yageo")
        (field (name "MANUFACTURER PART NUMBER") "RC0402FR-0710KL")
        (field (name "TOLERANCE") "1%")
        (field (name "TEMPERATURE COEFFICIENT") "100ppm/°C")
        (field (name "RESISTANCE") "10kR")
        (field (name "POWER RATING") "62.5mW")
        (field (name "CASE CODE (IMPERIAL)") "0402")
        (field (name "INTERNAL PART NUMBER") "R000016")
      )
      (libsource (lib "Altium_Lib_Standard") (part "RC0402FR-0710KL"))
    )
    (comp (ref "TP1")
      (value "RTC_TAMPER")
      (footprint "TP-SMD-CIRCULAR-0.5MM")
      (libsource (lib "Altium_Lib_Standard") (part "TESTPOINT_CIRCULAR_0.5MM"))
    )
    (comp (ref "TP2")
      (value "JTRSTN")
      (footprint "TP-SMD-CIRCULAR-0.5MM")
      (libsource (lib "Altium_Lib_Standard") (part "TESTPOINT_CIRCULAR_0.5MM"))
    )
    (comp (ref "U1")
      (value "CAT24C512WI-GT3")
      (footprint "SOIC-8-H1.75MM-P1.27MM-ONSEMI")
      (description "IC EEPROM 512KBIT 8BIT WORD I2C 1MHZ SOIC-8")
      (fields
        (field (name "MANUFACTURER") "ON Semiconductor")
        (field (name "INTERNAL PART NUMBER") "IC000050")
      )
      (libsource (lib "Altium_Lib_Standard") (part "CAT24C512WI-GT3"))
    )
    (comp (ref "U2")
      (value "STM32F103RCT6TR")
      (footprint "LQFP-64-10X10MM-H1.6MM-P0.5MM-ST")
      (description "IC MCU STM32F103 ARM CORTEX M3 32 BIT 72MHz 256K FLASH 48K RAM LQFP-64")
      (fields
        (field (name "MANUFACTURER") "STMicroelectronics")
        (field (name "INTERNAL PART NUMBER") "IC000049")
      )
      (libsource (lib "Altium_Lib_Standard") (part "STM32F103RCT6TR"))
    )
    (comp (ref "X1")
      (value "16MHz 9pF")
      (footprint "XTAL-SMD-4-SMD-3.2X2.5MM")
      (description "CRYSTAL 16MHZ 9PF SMD 4-SMD")
      (fields
        (field (name "CASE/PACKAGE") "4-SMD")
        (field (name "INTERNAL PART NUMBER") "XTAL000001")
        (field (name "FREQUENCY TOLERANCE") "10ppm")
        (field (name "LOAD CAPACITANCE") "9pF")
        (field (name "FREQUENCY") "16MHz")
      )
      (libsource (lib "Altium_Lib_Standard") (part "TSX-322516.0000MF18X-AC0"))
    )
    (comp (ref "X2")
      (value "32.768kHz 12.5pF")
      (footprint "XTAL-SMD-2-SMD-3.2X1.5MM")
      (description "CRYSTAL 32.768KHZ 12.5PF SMD 2-SMD")
      (fields
        (field (name "MANUFACTURER") "Epson")
        (field (name "MANUFACTURER PART NUMBER") "FC-13532.7680KA-A5")
        (field (name "INTERNAL PART NUMBER") "XTAL000005")
        (field (name "CASE/PACKAGE") "2-SMD")
        (field (name "FREQUENCY TOLERANCE") "20ppm")
        (field (name "LOAD CAPACITANCE") "12.5pF")
        (field (name "FREQUENCY") "32.768kHz")
      )
      (libsource (lib "Altium_Lib_Standard") (part "FC-13532.7680KA-A5"))
    )
  )
  (nets
    (net (code "1") (name "/MCU_BOOT0") (class "Default")
      (node (ref "R14") (pin "2") (pinfunction "2_2") (pintype "passive"))
      (node (ref "U2") (pin "60") (pinfunction "BOOT0_60") (pintype "input"))
    )
    (net (code "2") (name "/MCU_PA0_GPIO0") (class "Default")
      (node (ref "U2") (pin "14") (pinfunction "PA0-WKUP_14") (pintype "bidirectional"))
    )
    (net (code "3") (name "/MCU_PA1_AUX1") (class "Default")
      (node (ref "U2") (pin "15") (pinfunction "PA1_15") (pintype "bidirectional"))
    )
    (net (code "4") (name "/MCU_PA2_USART2_TX") (class "Default")
      (node (ref "U2") (pin "16") (pinfunction "PA2_16") (pintype "bidirectional"))
    )
    (net (code "5") (name "/MCU_PA3_USART2_RX") (class "Default")
      (node (ref "U2") (pin "17") (pinfunction "PA3_17") (pintype "bidirectional"))
    )
    (net (code "6") (name "/MCU_PA4_ERRORLED") (class "Default")
      (node (ref "R28") (pin "1") (pinfunction "1_1") (pintype "passive"))
      (node (ref "U2") (pin "20") (pinfunction "PA4_20") (pintype "bidirectional"))
    )
    (net (code "7") (name "/MCU_PA5_SPI1_SCK") (class "Default")
      (node (ref "U2") (pin "21") (pinfunction "PA5_21") (pintype "bidirectional"))
    )
    (net (code "8") (name "/MCU_PA6_SPI1_MISO") (class "Default")
      (node (ref "U2") (pin "22") (pinfunction "PA6_22") (pintype "bidirectional"))
    )
    (net (code "9") (name "/MCU_PA7_SPI1_MOSI") (class "Default")
      (node (ref "U2") (pin "23") (pinfunction "PA7_23") (pintype "bidirectional"))
    )
    (net (code "10") (name "/MCU_PA8_HWBIT0") (class "Default")
      (node (ref "R3") (pin "2") (pinfunction "2_2") (pintype "passive"))
      (node (ref "R8") (pin "1") (pinfunction "1_1") (pintype "passive"))
      (node (ref "U2") (pin "41") (pinfunction "PA8_41") (pintype "bidirectional"))
    )
    (net (code "11") (name "/MCU_PA9_USART1_TX") (class "Default")
      (node (ref "CN1") (pin "8") (pinfunction "DBGR-RX_8") (pintype "passive"))
      (node (ref "U2") (pin "42") (pinfunction "PA9_42") (pintype "bidirectional"))
    )
    (net (code "12") (name "/MCU_PA10_USART1_RX") (class "Default")
      (node (ref "CN1") (pin "9") (pinfunction "DBGR-TX_9") (pintype "passive"))
      (node (ref "U2") (pin "43") (pinfunction "PA10_43") (pintype "bidirectional"))
    )
    (net (code "13") (name "/MCU_PA13_JTAG_TMS_SWDIO") (class "Default")
      (node (ref "CN1") (pin "5") (pinfunction "TMS/SWDIO_5") (pintype "passive"))
      (node (ref "U2") (pin "46") (pinfunction "PA13_46") (pintype "bidirectional"))
    )
    (net (code "14") (name "/MCU_PA14_JTAG_TCK_SWCLK") (class "Default")
      (node (ref "CN1") (pin "3") (pinfunction "TCK/SWCLK_3") (pintype "passive"))
      (node (ref "U2") (pin "49") (pinfunction "PA14_49") (pintype "bidirectional"))
    )
    (net (code "15") (name "/MCU_PA15_JTAG_TDI") (class "Default")
      (node (ref "CN1") (pin "6") (pinfunction "TDI_6") (pintype "passive"))
      (node (ref "U2") (pin "50") (pinfunction "PA15_50") (pintype "bidirectional"))
    )
    (net (code "16") (name "/MCU_PB0_USERLED_0") (class "Default")
      (node (ref "R16") (pin "1") (pinfunction "1_1") (pintype "passive"))
      (node (ref "U2") (pin "26") (pinfunction "PB0_26") (pintype "bidirectional"))
    )
    (net (code "17") (name "/MCU_PB1_USERLED_1") (class "Default")
      (node (ref "R19") (pin "1") (pinfunction "1_1") (pintype "passive"))
      (node (ref "U2") (pin "27") (pinfunction "PB1_27") (pintype "bidirectional"))
    )
    (net (code "18") (name "/MCU_PB2_USERLED_2") (class "Default")
      (node (ref "R25") (pin "1") (pinfunction "1_1") (pintype "passive"))
      (node (ref "U2") (pin "28") (pinfunction "PB2_28") (pintype "bidirectional"))
    )
    (net (code "19") (name "/MCU_PB3_JTAG_TDO_TRACE_SWO") (class "Default")
      (node (ref "CN1") (pin "7") (pinfunction "TDO/SWO_7") (pintype "passive"))
      (node (ref "U2") (pin "55") (pinfunction "PB3_55") (pintype "bidirectional"))
    )
    (net (code "20") (name "/MCU_PB4_JTAG_TRSTn") (class "Default")
      (node (ref "TP2") (pin "1") (pinfunction "1_1") (pintype "passive"))
      (node (ref "U2") (pin "56") (pinfunction "PB4_56") (pintype "bidirectional"))
    )
    (net (code "21") (name "/MCU_PB5_EEPROM_WP") (class "Default")
      (node (ref "U1") (pin "7") (pinfunction "WP_7") (pintype "input"))
      (node (ref "U2") (pin "57") (pinfunction "PB5_57") (pintype "bidirectional"))
    )
    (net (code "22") (name "/MCU_PB6_I2C1_SCL") (class "Default")
      (node (ref "R1") (pin "2") (pinfunction "2_2") (pintype "passive"))
      (node (ref "U1") (pin "6") (pinfunction "SCL_6") (pintype "input"))
      (node (ref "U2") (pin "58") (pinfunction "PB6_58") (pintype "bidirectional"))
    )
    (net (code "23") (name "/MCU_PB7_I2C1_SDA") (class "Default")
      (node (ref "R2") (pin "2") (pinfunction "2_2") (pintype "passive"))
      (node (ref "U1") (pin "5") (pinfunction "SDA_5") (pintype "bidirectional"))
      (node (ref "U2") (pin "59") (pinfunction "PB7_59") (pintype "bidirectional"))
    )
    (net (code "24") (name "/MCU_PB8_HWBIT1") (class "Default")
      (node (ref "R4") (pin "2") (pinfunction "2_2") (pintype "passive"))
      (node (ref "R9") (pin "1") (pinfunction "1_1") (pintype "passive"))
      (node (ref "U2") (pin "61") (pinfunction "PB8_61") (pintype "bidirectional"))
    )
    (net (code "25") (name "/MCU_PB9_HWBIT2") (class "Default")
      (node (ref "R10") (pin "1") (pinfunction "1_1") (pintype "passive"))
      (node (ref "R5") (pin "2") (pinfunction "2_2") (pintype "passive"))
      (node (ref "U2") (pin "62") (pinfunction "PB9_62") (pintype "bidirectional"))
    )
    (net (code "26") (name "/MCU_PB10_I2C2_SCL") (class "Default")
      (node (ref "R24") (pin "2") (pinfunction "2_2") (pintype "passive"))
      (node (ref "U2") (pin "29") (pinfunction "PB10_29") (pintype "bidirectional"))
    )
    (net (code "27") (name "/MCU_PB11_I2C2_SDA") (class "Default")
      (node (ref "R23") (pin "2") (pinfunction "2_2") (pintype "passive"))
      (node (ref "U2") (pin "30") (pinfunction "PB11_30") (pintype "bidirectional"))
    )
    (net (code "28") (name "/MCU_PB12_HWBIT3") (class "Default")
      (node (ref "R11") (pin "1") (pinfunction "1_1") (pintype "passive"))
      (node (ref "R6") (pin "2") (pinfunction "2_2") (pintype "passive"))
      (node (ref "U2") (pin "33") (pinfunction "PB12_33") (pintype "bidirectional"))
    )
    (net (code "29") (name "/MCU_PB13_SPI2_SCK") (class "Default")
      (node (ref "U2") (pin "34") (pinfunction "PB13_34") (pintype "bidirectional"))
    )
    (net (code "30") (name "/MCU_PB14_SPI2_MISO") (class "Default")
      (node (ref "U2") (pin "35") (pinfunction "PB14_35") (pintype "bidirectional"))
    )
    (net (code "31") (name "/MCU_PB15_SPI2_MOSI") (class "Default")
      (node (ref "U2") (pin "36") (pinfunction "PB15_36") (pintype "bidirectional"))
    )
    (net (code "32") (name "/MCU_PC0_GPIO1") (class "Default")
      (node (ref "U2") (pin "8") (pinfunction "PC0_8") (pintype "bidirectional"))
    )
    (net (code "33") (name "/MCU_PC1_GPIO2") (class "Default")
      (node (ref "U2") (pin "9") (pinfunction "PC1_9") (pintype "bidirectional"))
    )
    (net (code "34") (name "/MCU_PC2_GPIO3") (class "Default")
      (node (ref "U2") (pin "10") (pinfunction "PC2_10") (pintype "bidirectional"))
    )
    (net (code "35") (name "/MCU_PC3_GPIO4") (class "Default")
      (node (ref "U2") (pin "11") (pinfunction "PC3_11") (pintype "bidirectional"))
    )
    (net (code "36") (name "/MCU_PC4_GPIO5") (class "Default")
      (node (ref "U2") (pin "24") (pinfunction "PC4_24") (pintype "bidirectional"))
    )
    (net (code "37") (name "/MCU_PC5_GPIO6") (class "Default")
      (node (ref "U2") (pin "25") (pinfunction "PC5_25") (pintype "bidirectional"))
    )
    (net (code "38") (name "/MCU_PC6_HWBIT4") (class "Default")
      (node (ref "R12") (pin "1") (pinfunction "1_1") (pintype "passive"))
      (node (ref "R7") (pin "2") (pinfunction "2_2") (pintype "passive"))
      (node (ref "U2") (pin "37") (pinfunction "PC6_37") (pintype "bidirectional"))
    )
    (net (code "39") (name "/MCU_PC7_GPIO8") (class "Default")
      (node (ref "U2") (pin "38") (pinfunction "PC7_38") (pintype "bidirectional"))
    )
    (net (code "40") (name "/MCU_PC8_GPIO9") (class "Default")
      (node (ref "U2") (pin "39") (pinfunction "PC8_39") (pintype "bidirectional"))
    )
    (net (code "41") (name "/MCU_PC9_GPIO10") (class "Default")
      (node (ref "U2") (pin "40") (pinfunction "PC9_40") (pintype "bidirectional"))
    )
    (net (code "42") (name "/MCU_PC10_GPIO11") (class "Default")
      (node (ref "U2") (pin "51") (pinfunction "PC10_51") (pintype "bidirectional"))
    )
    (net (code "43") (name "/MCU_PC11_GPIO12") (class "Default")
      (node (ref "U2") (pin "52") (pinfunction "PC11_52") (pintype "bidirectional"))
    )
    (net (code "44") (name "/MCU_PC12_GPIO13") (class "Default")
      (node (ref "U2") (pin "53") (pinfunction "PC12_53") (pintype "bidirectional"))
    )
    (net (code "45") (name "/MCU_PC13_RTC_TAMPER") (class "Default")
      (node (ref "TP1") (pin "1") (pinfunction "1_1") (pintype "passive"))
      (node (ref "U2") (pin "2") (pinfunction "PC13-TAMPERRTC_2") (pintype "bidirectional"))
    )
    (net (code "46") (name "/MCU_PD2_GPIO7") (class "Default")
      (node (ref "U2") (pin "54") (pinfunction "PD2_54") (pintype "bidirectional"))
    )
    (net (code "47") (name "/MCU_RESETn") (class "Default")
      (node (ref "CN1") (pin "1") (pinfunction "RESET_1") (pintype "passive"))
      (node (ref "R15") (pin "2") (pinfunction "2_2") (pintype "passive"))
      (node (ref "U2") (pin "7") (pinfunction "NRST_7") (pintype "bidirectional"))
    )
    (net (code "48") (name "/MCU_USB_D_N") (class "Default")
      (node (ref "U2") (pin "44") (pinfunction "PA11_44") (pintype "bidirectional"))
    )
    (net (code "49") (name "/MCU_USB_D_P") (class "Default")
      (node (ref "R20") (pin "2") (pinfunction "2_2") (pintype "passive"))
      (node (ref "U2") (pin "45") (pinfunction "PA12_45") (pintype "bidirectional"))
    )
    (net (code "50") (name "/MCU_XTAL32_OSC_IN") (class "Default")
      (node (ref "C5") (pin "1") (pinfunction "1_1") (pintype "passive"))
      (node (ref "U2") (pin "3") (pinfunction "PC14-OSC32_IN_3") (pintype "bidirectional"))
      (node (ref "X2") (pin "1") (pinfunction "1_1") (pintype "passive"))
    )
    (net (code "51") (name "/MCU_XTAL32_OSC_OUT") (class "Default")
      (node (ref "C4") (pin "1") (pinfunction "1_1") (pintype "passive"))
      (node (ref "U2") (pin "4") (pinfunction "PC15-OSC32_OUT_4") (pintype "bidirectional"))
      (node (ref "X2") (pin "2") (pinfunction "2_2") (pintype "passive"))
    )
    (net (code "52") (name "/MCU_XTAL_OSC_IN") (class "Default")
      (node (ref "C3") (pin "1") (pinfunction "1_1") (pintype "passive"))
      (node (ref "U2") (pin "5") (pinfunction "PD0-OSC_IN_5") (pintype "bidirectional"))
      (node (ref "X1") (pin "1") (pinfunction "1_1") (pintype "passive"))
    )
    (net (code "53") (name "/MCU_XTAL_OSC_OUT") (class "Default")
      (node (ref "C2") (pin "1") (pinfunction "1_1") (pintype "passive"))
      (node (ref "U2") (pin "6") (pinfunction "PD1-OSC_OUT_6") (pintype "bidirectional"))
      (node (ref "X1") (pin "3") (pinfunction "3_3") (pintype "passive"))
    )
    (net (code "54") (name "3V3") (class "Default")
      (node (ref "C1") (pin "1") (pinfunction "1_1") (pintype "passive"))
      (node (ref "C10") (pin "1") (pinfunction "1_1") (pintype "passive"))
      (node (ref "C11") (pin "1") (pinfunction "1_1") (pintype "passive"))
      (node (ref "C12") (pin "1") (pinfunction "1_1") (pintype "passive"))
      (node (ref "C13") (pin "1") (pinfunction "1_1") (pintype "passive"))
      (node (ref "C14") (pin "1") (pinfunction "1_1") (pintype "passive"))
      (node (ref "C15") (pin "1") (pinfunction "1_1") (pintype "passive"))
      (node (ref "CN1") (pin "10") (pinfunction "VCC_10") (pintype "passive"))
      (node (ref "FB1") (pin "1") (pinfunction "1_1") (pintype "passive"))
      (node (ref "R1") (pin "1") (pinfunction "1_1") (pintype "passive"))
      (node (ref "R13") (pin "1") (pinfunction "1_1") (pintype "passive"))
      (node (ref "R15") (pin "1") (pinfunction "1_1") (pintype "passive"))
      (node (ref "R18") (pin "1") (pinfunction "1_1") (pintype "passive"))
      (node (ref "R2") (pin "1") (pinfunction "1_1") (pintype "passive"))
      (node (ref "R20") (pin "1") (pinfunction "1_1") (pintype "passive"))
      (node (ref "R22") (pin "1") (pinfunction "1_1") (pintype "passive"))
      (node (ref "R23") (pin "1") (pinfunction "1_1") (pintype "passive"))
      (node (ref "R24") (pin "1") (pinfunction "1_1") (pintype "passive"))
      (node (ref "R27") (pin "1") (pinfunction "1_1") (pintype "passive"))
      (node (ref "R3") (pin "1") (pinfunction "1_1") (pintype "passive"))
      (node (ref "R4") (pin "1") (pinfunction "1_1") (pintype "passive"))
      (node (ref "R5") (pin "1") (pinfunction "1_1") (pintype "passive"))
      (node (ref "R6") (pin "1") (pinfunction "1_1") (pintype "passive"))
      (node (ref "R7") (pin "1") (pinfunction "1_1") (pintype "passive"))
      (node (ref "U1") (pin "8") (pinfunction "VCC_8") (pintype "power_in"))
      (node (ref "U2") (pin "19") (pinfunction "VDD_4_19") (pintype "power_in"))
      (node (ref "U2") (pin "32") (pinfunction "VDD_1_32") (pintype "power_in"))
      (node (ref "U2") (pin "48") (pinfunction "VDD_2_48") (pintype "power_in"))
      (node (ref "U2") (pin "64") (pinfunction "VDD_3_64") (pintype "power_in"))
    )
    (net (code "55") (name "3V3_VDDA_MCU") (class "Default")
      (node (ref "C6") (pin "1") (pinfunction "1_1") (pintype "passive"))
      (node (ref "C7") (pin "1") (pinfunction "1_1") (pintype "passive"))
      (node (ref "FB1") (pin "2") (pinfunction "2_2") (pintype "passive"))
      (node (ref "U2") (pin "13") (pinfunction "VDDA_13") (pintype "power_in"))
    )
    (net (code "56") (name "GND") (class "Default")
      (node (ref "C1") (pin "2") (pinfunction "2_2") (pintype "passive"))
      (node (ref "C10") (pin "2") (pinfunction "2_2") (pintype "passive"))
      (node (ref "C11") (pin "2") (pinfunction "2_2") (pintype "passive"))
      (node (ref "C12") (pin "2") (pinfunction "2_2") (pintype "passive"))
      (node (ref "C13") (pin "2") (pinfunction "2_2") (pintype "passive"))
      (node (ref "C14") (pin "2") (pinfunction "2_2") (pintype "passive"))
      (node (ref "C15") (pin "2") (pinfunction "2_2") (pintype "passive"))
      (node (ref "C2") (pin "2") (pinfunction "2_2") (pintype "passive"))
      (node (ref "C3") (pin "2") (pinfunction "2_2") (pintype "passive"))
      (node (ref "C4") (pin "2") (pinfunction "2_2") (pintype "passive"))
      (node (ref "C5") (pin "2") (pinfunction "2_2") (pintype "passive"))
      (node (ref "C6") (pin "2") (pinfunction "2_2") (pintype "passive"))
      (node (ref "C7") (pin "2") (pinfunction "2_2") (pintype "passive"))
      (node (ref "C8") (pin "2") (pinfunction "2_2") (pintype "passive"))
      (node (ref "C9") (pin "2") (pinfunction "2_2") (pintype "passive"))
      (node (ref "CN1") (pin "2") (pinfunction "GND_2") (pintype "passive"))
      (node (ref "CN1") (pin "4") (pinfunction "GND_4") (pintype "passive"))
      (node (ref "MH1") (pin "1") (pinfunction "1_1") (pintype "passive"))
      (node (ref "MH2") (pin "1") (pinfunction "1_1") (pintype "passive"))
      (node (ref "Q1") (pin "2") (pinfunction "Source_2") (pintype "passive"))
      (node (ref "Q2") (pin "2") (pinfunction "Source_2") (pintype "passive"))
      (node (ref "Q3") (pin "2") (pinfunction "Source_2") (pintype "passive"))
      (node (ref "Q4") (pin "2") (pinfunction "Source_2") (pintype "passive"))
      (node (ref "R10") (pin "2") (pinfunction "2_2") (pintype "passive"))
      (node (ref "R11") (pin "2") (pinfunction "2_2") (pintype "passive"))
      (node (ref "R12") (pin "2") (pinfunction "2_2") (pintype "passive"))
      (node (ref "R14") (pin "1") (pinfunction "1_1") (pintype "passive"))
      (node (ref "R17") (pin "2") (pinfunction "2_2") (pintype "passive"))
      (node (ref "R21") (pin "2") (pinfunction "2_2") (pintype "passive"))
      (node (ref "R26") (pin "2") (pinfunction "2_2") (pintype "passive"))
      (node (ref "R29") (pin "2") (pinfunction "2_2") (pintype "passive"))
      (node (ref "R8") (pin "2") (pinfunction "2_2") (pintype "passive"))
      (node (ref "R9") (pin "2") (pinfunction "2_2") (pintype "passive"))
      (node (ref "U1") (pin "1") (pinfunction "A0_1") (pintype "input"))
      (node (ref "U1") (pin "2") (pinfunction "A1_2") (pintype "input"))
      (node (ref "U1") (pin "3") (pinfunction "A2_3") (pintype "input"))
      (node (ref "U1") (pin "4") (pinfunction "VSS_4") (pintype "power_in"))
      (node (ref "U2") (pin "12") (pinfunction "VSSA_12") (pintype "power_in"))
      (node (ref "U2") (pin "18") (pinfunction "VSS_4_18") (pintype "power_in"))
      (node (ref "U2") (pin "31") (pinfunction "VSS_1_31") (pintype "power_in"))
      (node (ref "U2") (pin "47") (pinfunction "VSS_2_47") (pintype "power_in"))
      (node (ref "U2") (pin "63") (pinfunction "VSS_3_63") (pintype "power_in"))
    )
    (net (code "57") (name "Net-(D1-Pad2)") (class "Default")
      (node (ref "D1") (pin "2") (pinfunction "2_2") (pintype "passive"))
      (node (ref "R13") (pin "2") (pinfunction "2_2") (pintype "passive"))
    )
    (net (code "58") (name "Net-(D2-Pad2)") (class "Default")
      (node (ref "D2") (pin "2") (pinfunction "2_2") (pintype "passive"))
      (node (ref "R18") (pin "2") (pinfunction "2_2") (pintype "passive"))
    )
    (net (code "59") (name "Net-(D3-Pad2)") (class "Default")
      (node (ref "D3") (pin "2") (pinfunction "2_2") (pintype "passive"))
      (node (ref "R22") (pin "2") (pinfunction "2_2") (pintype "passive"))
    )
    (net (code "60") (name "Net-(D4-Pad2)") (class "Default")
      (node (ref "D4") (pin "2") (pinfunction "2_2") (pintype "passive"))
      (node (ref "R27") (pin "2") (pinfunction "2_2") (pintype "passive"))
    )
    (net (code "61") (name "Net-(Q1-Drain)") (class "Default")
      (node (ref "D1") (pin "1") (pinfunction "1_1") (pintype "passive"))
      (node (ref "Q1") (pin "3") (pinfunction "Drain_3") (pintype "passive"))
    )
    (net (code "62") (name "Net-(Q1-Gate)") (class "Default")
      (node (ref "Q1") (pin "1") (pinfunction "Gate_1") (pintype "passive"))
      (node (ref "R16") (pin "2") (pinfunction "2_2") (pintype "passive"))
      (node (ref "R17") (pin "1") (pinfunction "1_1") (pintype "passive"))
    )
    (net (code "63") (name "Net-(Q2-Drain)") (class "Default")
      (node (ref "D2") (pin "1") (pinfunction "1_1") (pintype "passive"))
      (node (ref "Q2") (pin "3") (pinfunction "Drain_3") (pintype "passive"))
    )
    (net (code "64") (name "Net-(Q2-Gate)") (class "Default")
      (node (ref "Q2") (pin "1") (pinfunction "Gate_1") (pintype "passive"))
      (node (ref "R19") (pin "2") (pinfunction "2_2") (pintype "passive"))
      (node (ref "R21") (pin "1") (pinfunction "1_1") (pintype "passive"))
    )
    (net (code "65") (name "Net-(Q3-Drain)") (class "Default")
      (node (ref "D3") (pin "1") (pinfunction "1_1") (pintype "passive"))
      (node (ref "Q3") (pin "3") (pinfunction "Drain_3") (pintype "passive"))
    )
    (net (code "66") (name "Net-(Q3-Gate)") (class "Default")
      (node (ref "Q3") (pin "1") (pinfunction "Gate_1") (pintype "passive"))
      (node (ref "R25") (pin "2") (pinfunction "2_2") (pintype "passive"))
      (node (ref "R26") (pin "1") (pinfunction "1_1") (pintype "passive"))
    )
    (net (code "67") (name "Net-(Q4-Drain)") (class "Default")
      (node (ref "D4") (pin "1") (pinfunction "1_1") (pintype "passive"))
      (node (ref "Q4") (pin "3") (pinfunction "Drain_3") (pintype "passive"))
    )
    (net (code "68") (name "Net-(Q4-Gate)") (class "Default")
      (node (ref "Q4") (pin "1") (pinfunction "Gate_1") (pintype "passive"))
      (node (ref "R28") (pin "2") (pinfunction "2_2") (pintype "passive"))
      (node (ref "R29") (pin "1") (pinfunction "1_1") (pintype "passive"))
    )
    (net (code "69") (name "VBAT_MCU") (class "Default")
      (node (ref "C8") (pin "1") (pinfunction "1_1") (pintype "passive"))
      (node (ref "C9") (pin "1") (pinfunction "1_1") (pintype "passive"))
      (node (ref "U2") (pin "1") (pinfunction "VBAT_1") (pintype "power_in"))
    )
  )
)
